# MaTouch_ESP32-S3_AMOLED_AI_CAMERA_v1_1.net
KiCad netlist of a schematic drawn in EAGLE
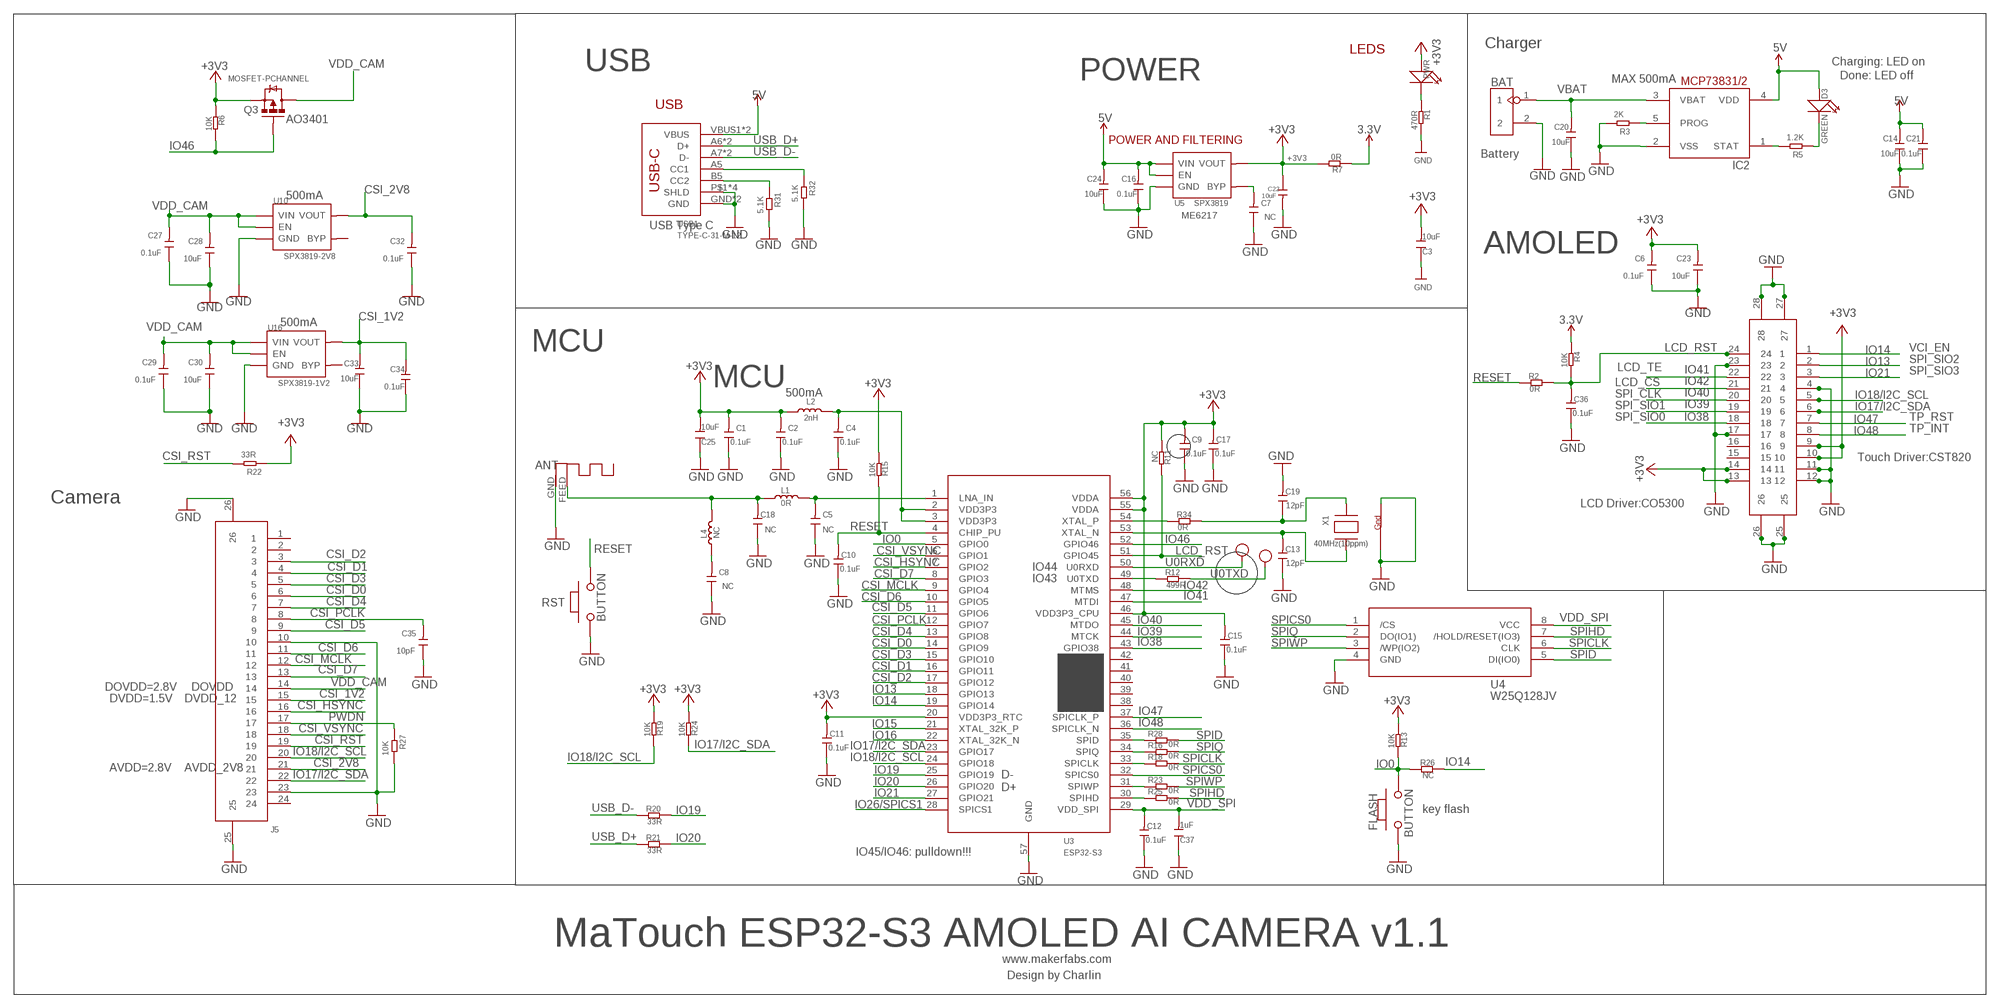
[diagram p0: schematic, sheet 1]

(export (version "E")
  (design (tool "Eeschema 10.0.6"))
  (components
    (comp (ref "ANT1")
      (value "ANTENNA")
      (footprint "eagle-import:RN-ANT")
      (libsource (lib "eagle-import") (part "ANTENNA"))
    )
    (comp (ref "BAT")
      (value "HEADER-2P-2.0")
      (footprint "eagle-import:2P-2.0")
      (libsource (lib "eagle-import") (part "HEADER-2P-2.0"))
    )
    (comp (ref "C1")
      (value "0.1uF")
      (footprint "eagle-import:DISCRETE_C0402")
      (libsource (lib "eagle-import") (part "DISCRETE_C-0402"))
    )
    (comp (ref "C2")
      (value "0.1uF")
      (footprint "eagle-import:DISCRETE_C0402")
      (libsource (lib "eagle-import") (part "DISCRETE_C-0402"))
    )
    (comp (ref "C3")
      (value "10uF")
      (footprint "eagle-import:DISCRETE_C0603")
      (libsource (lib "eagle-import") (part "DISCRETE_C-0603"))
    )
    (comp (ref "C4")
      (value "0.1uF")
      (footprint "eagle-import:DISCRETE_C0402")
      (libsource (lib "eagle-import") (part "DISCRETE_C-0402"))
    )
    (comp (ref "C5")
      (value "NC")
      (footprint "eagle-import:DISCRETE_C0402")
      (libsource (lib "eagle-import") (part "DISCRETE_C-0402"))
    )
    (comp (ref "C6")
      (value "0.1uF")
      (footprint "eagle-import:DISCRETE_C0402")
      (libsource (lib "eagle-import") (part "DISCRETE_C-0402"))
    )
    (comp (ref "C7")
      (value "NC")
      (footprint "eagle-import:DISCRETE_C0402")
      (libsource (lib "eagle-import") (part "DISCRETE_C-0402"))
    )
    (comp (ref "C8")
      (value "NC")
      (footprint "eagle-import:DISCRETE_C0402")
      (libsource (lib "eagle-import") (part "DISCRETE_C-0402"))
    )
    (comp (ref "C9")
      (value "0.1uF")
      (footprint "eagle-import:DISCRETE_C0402")
      (libsource (lib "eagle-import") (part "DISCRETE_C-0402"))
    )
    (comp (ref "C10")
      (value "0.1uF")
      (footprint "eagle-import:DISCRETE_C0402")
      (libsource (lib "eagle-import") (part "DISCRETE_C-0402"))
    )
    (comp (ref "C11")
      (value "0.1uF")
      (footprint "eagle-import:DISCRETE_C0402")
      (libsource (lib "eagle-import") (part "DISCRETE_C-0402"))
    )
    (comp (ref "C12")
      (value "0.1uF")
      (footprint "eagle-import:DISCRETE_C0402")
      (libsource (lib "eagle-import") (part "DISCRETE_C-0402"))
    )
    (comp (ref "C13")
      (value "12pF")
      (footprint "eagle-import:DISCRETE_C0402")
      (libsource (lib "eagle-import") (part "DISCRETE_C-0402"))
    )
    (comp (ref "C14")
      (value "10uF")
      (footprint "eagle-import:DISCRETE_C0402")
      (libsource (lib "eagle-import") (part "DISCRETE_C-0402"))
    )
    (comp (ref "C15")
      (value "0.1uF")
      (footprint "eagle-import:DISCRETE_C0402")
      (libsource (lib "eagle-import") (part "DISCRETE_C-0402"))
    )
    (comp (ref "C16")
      (value "0.1uF")
      (footprint "eagle-import:DISCRETE_C0402")
      (libsource (lib "eagle-import") (part "DISCRETE_C-0402"))
    )
    (comp (ref "C17")
      (value "0.1uF")
      (footprint "eagle-import:DISCRETE_C0402")
      (libsource (lib "eagle-import") (part "DISCRETE_C-0402"))
    )
    (comp (ref "C18")
      (value "NC")
      (footprint "eagle-import:DISCRETE_C0402")
      (libsource (lib "eagle-import") (part "DISCRETE_C-0402"))
    )
    (comp (ref "C19")
      (value "12pF")
      (footprint "eagle-import:DISCRETE_C0402")
      (libsource (lib "eagle-import") (part "DISCRETE_C-0402"))
    )
    (comp (ref "C20")
      (value "10uF")
      (footprint "eagle-import:DISCRETE_C0402")
      (libsource (lib "eagle-import") (part "DISCRETE_C-0402"))
    )
    (comp (ref "C21")
      (value "0.1uF")
      (footprint "eagle-import:DISCRETE_C0402")
      (libsource (lib "eagle-import") (part "DISCRETE_C-0402"))
    )
    (comp (ref "C22")
      (value "10uF")
      (footprint "eagle-import:0603")
      (libsource (lib "eagle-import") (part "C-0603"))
    )
    (comp (ref "C23")
      (value "10uF")
      (footprint "eagle-import:DISCRETE_C0402")
      (libsource (lib "eagle-import") (part "DISCRETE_C-0402"))
    )
    (comp (ref "C24")
      (value "10uF")
      (footprint "eagle-import:DISCRETE_C0402")
      (libsource (lib "eagle-import") (part "DISCRETE_C-0402"))
    )
    (comp (ref "C25")
      (value "10uF")
      (footprint "eagle-import:DISCRETE_C0603")
      (libsource (lib "eagle-import") (part "DISCRETE_C-0603"))
    )
    (comp (ref "C27")
      (value "0.1uF")
      (footprint "eagle-import:DISCRETE_C0402")
      (libsource (lib "eagle-import") (part "DISCRETE_C-0402"))
    )
    (comp (ref "C28")
      (value "10uF")
      (footprint "eagle-import:DISCRETE_C0402")
      (libsource (lib "eagle-import") (part "DISCRETE_C-0402"))
    )
    (comp (ref "C29")
      (value "0.1uF")
      (footprint "eagle-import:DISCRETE_C0402")
      (libsource (lib "eagle-import") (part "DISCRETE_C-0402"))
    )
    (comp (ref "C30")
      (value "10uF")
      (footprint "eagle-import:DISCRETE_C0402")
      (libsource (lib "eagle-import") (part "DISCRETE_C-0402"))
    )
    (comp (ref "C32")
      (value "0.1uF")
      (footprint "eagle-import:DISCRETE_C0402")
      (libsource (lib "eagle-import") (part "DISCRETE_C-0402"))
    )
    (comp (ref "C33")
      (value "10uF")
      (footprint "eagle-import:DISCRETE_C0402")
      (libsource (lib "eagle-import") (part "DISCRETE_C-0402"))
    )
    (comp (ref "C34")
      (value "0.1uF")
      (footprint "eagle-import:DISCRETE_C0402")
      (libsource (lib "eagle-import") (part "DISCRETE_C-0402"))
    )
    (comp (ref "C35")
      (value "10pF")
      (footprint "eagle-import:DISCRETE_C0402")
      (libsource (lib "eagle-import") (part "DISCRETE_C-0402"))
    )
    (comp (ref "C36")
      (value "0.1uF")
      (footprint "eagle-import:DISCRETE_C0402")
      (libsource (lib "eagle-import") (part "DISCRETE_C-0402"))
    )
    (comp (ref "C37")
      (value "1uF")
      (footprint "eagle-import:DISCRETE_C0603")
      (libsource (lib "eagle-import") (part "DISCRETE_C-0603"))
    )
    (comp (ref "D3")
      (value "GREEN")
      (footprint "eagle-import:DISCRETE_LED-0603")
      (libsource (lib "eagle-import") (part "DISCRETE_LED0603"))
    )
    (comp (ref "FLASH")
      (value "BUTTON")
      (footprint "eagle-import:157SW")
      (libsource (lib "eagle-import") (part "PB157"))
    )
    (comp (ref "IC2")
      (value "TP4054")
      (footprint "eagle-import:SOT23-5L")
      (libsource (lib "eagle-import") (part "MCP73831/OT"))
    )
    (comp (ref "J1")
      (value "OK-14GF024-04/AXE524127")
      (footprint "eagle-import:SMD24-50P-730L250W77H")
      (libsource (lib "eagle-import") (part "AXE524127"))
    )
    (comp (ref "J5")
      (value "FPC-24P")
      (footprint "eagle-import:SMD26-50P-1760L450W")
      (libsource (lib "eagle-import") (part "FPC-24P"))
    )
    (comp (ref "L1")
      (value "0R")
      (footprint "eagle-import:DISCRETE_L0402")
      (libsource (lib "eagle-import") (part "DISCRETE_L0402"))
    )
    (comp (ref "L2")
      (value "2nH")
      (footprint "eagle-import:DISCRETE_L0603")
      (libsource (lib "eagle-import") (part "DISCRETE_L0603"))
    )
    (comp (ref "L4")
      (value "NC")
      (footprint "eagle-import:DISCRETE_L0402")
      (libsource (lib "eagle-import") (part "DISCRETE_L0402"))
    )
    (comp (ref "PWR")
      (value "DISCRETE_LED0603")
      (footprint "eagle-import:DISCRETE_LED-0603")
      (libsource (lib "eagle-import") (part "DISCRETE_LED0603"))
    )
    (comp (ref "Q3")
      (value "MOSFET-PCHANNEL")
      (footprint "eagle-import:SOT23-3")
      (libsource (lib "eagle-import") (part "MOSFET-PCHANNEL"))
    )
    (comp (ref "R1")
      (value "470R")
      (footprint "eagle-import:DISCRETE_R0402")
      (libsource (lib "eagle-import") (part "DISCRETE_R-0402"))
    )
    (comp (ref "R2")
      (value "0R")
      (footprint "eagle-import:DISCRETE_R0402")
      (libsource (lib "eagle-import") (part "DISCRETE_R-0402"))
    )
    (comp (ref "R3")
      (value "2K")
      (footprint "eagle-import:DISCRETE_R0402")
      (libsource (lib "eagle-import") (part "DISCRETE_R-0402"))
    )
    (comp (ref "R4")
      (value "10K")
      (footprint "eagle-import:DISCRETE_R0402")
      (libsource (lib "eagle-import") (part "DISCRETE_R-0402"))
    )
    (comp (ref "R5")
      (value "1.2K")
      (footprint "eagle-import:DISCRETE_R0402")
      (libsource (lib "eagle-import") (part "DISCRETE_R-0402"))
    )
    (comp (ref "R6")
      (value "10K")
      (footprint "eagle-import:DISCRETE_R0402")
      (libsource (lib "eagle-import") (part "DISCRETE_R-0402"))
    )
    (comp (ref "R7")
      (value "0R")
      (footprint "eagle-import:DISCRETE_R0402")
      (libsource (lib "eagle-import") (part "DISCRETE_R-0402"))
    )
    (comp (ref "R11")
      (value "NC")
      (footprint "eagle-import:DISCRETE_R0402")
      (libsource (lib "eagle-import") (part "DISCRETE_R-0402"))
    )
    (comp (ref "R12")
      (value "499R")
      (footprint "eagle-import:DISCRETE_R0402")
      (libsource (lib "eagle-import") (part "DISCRETE_R-0402"))
    )
    (comp (ref "R13")
      (value "10K")
      (footprint "eagle-import:DISCRETE_R0402")
      (libsource (lib "eagle-import") (part "DISCRETE_R-0402"))
    )
    (comp (ref "R15")
      (value "10K")
      (footprint "eagle-import:DISCRETE_R0402")
      (libsource (lib "eagle-import") (part "DISCRETE_R-0402"))
    )
    (comp (ref "R16")
      (value "0R")
      (footprint "eagle-import:DISCRETE_R0402")
      (libsource (lib "eagle-import") (part "DISCRETE_R-0402"))
    )
    (comp (ref "R18")
      (value "0R")
      (footprint "eagle-import:DISCRETE_R0402")
      (libsource (lib "eagle-import") (part "DISCRETE_R-0402"))
    )
    (comp (ref "R19")
      (value "10K")
      (footprint "eagle-import:DISCRETE_R0402")
      (libsource (lib "eagle-import") (part "DISCRETE_R-0402"))
    )
    (comp (ref "R20")
      (value "33R")
      (footprint "eagle-import:DISCRETE_R0402")
      (libsource (lib "eagle-import") (part "DISCRETE_R-0402"))
    )
    (comp (ref "R21")
      (value "33R")
      (footprint "eagle-import:DISCRETE_R0402")
      (libsource (lib "eagle-import") (part "DISCRETE_R-0402"))
    )
    (comp (ref "R22")
      (value "33R")
      (footprint "eagle-import:DISCRETE_R0402")
      (libsource (lib "eagle-import") (part "DISCRETE_R-0402"))
    )
    (comp (ref "R23")
      (value "0R")
      (footprint "eagle-import:DISCRETE_R0402")
      (libsource (lib "eagle-import") (part "DISCRETE_R-0402"))
    )
    (comp (ref "R24")
      (value "10K")
      (footprint "eagle-import:DISCRETE_R0402")
      (libsource (lib "eagle-import") (part "DISCRETE_R-0402"))
    )
    (comp (ref "R25")
      (value "0R")
      (footprint "eagle-import:DISCRETE_R0402")
      (libsource (lib "eagle-import") (part "DISCRETE_R-0402"))
    )
    (comp (ref "R26")
      (value "NC")
      (footprint "eagle-import:DISCRETE_R0402")
      (libsource (lib "eagle-import") (part "DISCRETE_R-0402"))
    )
    (comp (ref "R27")
      (value "10K")
      (footprint "eagle-import:DISCRETE_R0402")
      (libsource (lib "eagle-import") (part "DISCRETE_R-0402"))
    )
    (comp (ref "R28")
      (value "0R")
      (footprint "eagle-import:DISCRETE_R0402")
      (libsource (lib "eagle-import") (part "DISCRETE_R-0402"))
    )
    (comp (ref "R31")
      (value "5.1K")
      (footprint "eagle-import:DISCRETE_R0402")
      (libsource (lib "eagle-import") (part "DISCRETE_R-0402"))
    )
    (comp (ref "R32")
      (value "5.1K")
      (footprint "eagle-import:DISCRETE_R0402")
      (libsource (lib "eagle-import") (part "DISCRETE_R-0402"))
    )
    (comp (ref "R34")
      (value "0R")
      (footprint "eagle-import:DISCRETE_R0402")
      (libsource (lib "eagle-import") (part "DISCRETE_R-0402"))
    )
    (comp (ref "RST")
      (value "BUTTON")
      (footprint "eagle-import:157SW")
      (libsource (lib "eagle-import") (part "PB157"))
    )
    (comp (ref "RX")
      (value "TEST-POINT'4545'")
      (footprint "eagle-import:TP-D45MIL")
      (fields (field (name "PARTNO") "DNP") (field (name "PARTNO_1") "DNP"))
      (libsource (lib "eagle-import") (part "TEST-POINT'4545'"))
    )
    (comp (ref "TX")
      (value "TEST-POINT'4545'")
      (footprint "eagle-import:TP-D45MIL")
      (fields (field (name "PARTNO") "DNP") (field (name "PARTNO_1") "DNP"))
      (libsource (lib "eagle-import") (part "TEST-POINT'4545'"))
    )
    (comp (ref "U3")
      (value "ESP32-S3")
      (footprint "eagle-import:QFN56-7_7MM")
      (libsource (lib "eagle-import") (part "ESP32-S3"))
    )
    (comp (ref "U4")
      (value "W25Q128JV")
      (footprint "eagle-import:SOIC-8-208MIL")
      (libsource (lib "eagle-import") (part "W25Q128JV"))
    )
    (comp (ref "U5")
      (value "SPX3819")
      (footprint "eagle-import:SOT23-5")
      (libsource (lib "eagle-import") (part "SPX3819"))
    )
    (comp (ref "U10")
      (value "SPX3819-2V8")
      (footprint "eagle-import:SOT23-5")
      (libsource (lib "eagle-import") (part "SPX3819"))
    )
    (comp (ref "U16")
      (value "SPX3819-1V2")
      (footprint "eagle-import:SOT23-5")
      (libsource (lib "eagle-import") (part "SPX3819"))
    )
    (comp (ref "USB1")
      (value "TYPE-C-31-M-12")
      (footprint "eagle-import:TYPE-C-31-M-12")
      (libsource (lib "eagle-import") (part "TYPE-C-31-M-12"))
    )
    (comp (ref "X1")
      (value "40MHz(10ppm)")
      (footprint "eagle-import:NX3225")
      (libsource (lib "eagle-import") (part "XTAL-4-3225"))
    )
  )
  (nets
    (net (code "1") (name "+3V3") (class "Default")
      (node (ref "C1") (pin "2") (pinfunction "2_2") (pintype "passive"))
      (node (ref "C11") (pin "2") (pinfunction "2_2") (pintype "passive"))
      (node (ref "C15") (pin "2") (pinfunction "2_2") (pintype "passive"))
      (node (ref "C17") (pin "2") (pinfunction "2_2") (pintype "passive"))
      (node (ref "C2") (pin "2") (pinfunction "2_2") (pintype "passive"))
      (node (ref "C22") (pin "1") (pinfunction "1_1") (pintype "passive"))
      (node (ref "C23") (pin "2") (pinfunction "2_2") (pintype "passive"))
      (node (ref "C25") (pin "2") (pinfunction "2_2") (pintype "passive"))
      (node (ref "C3") (pin "2") (pinfunction "2_2") (pintype "passive"))
      (node (ref "C6") (pin "2") (pinfunction "2_2") (pintype "passive"))
      (node (ref "C9") (pin "2") (pinfunction "2_2") (pintype "passive"))
      (node (ref "J1") (pin "10") (pinfunction "10_10") (pintype "bidirectional"))
      (node (ref "J1") (pin "13") (pinfunction "13_13") (pintype "bidirectional"))
      (node (ref "J1") (pin "14") (pinfunction "14_14") (pintype "bidirectional"))
      (node (ref "J1") (pin "9") (pinfunction "9_9") (pintype "bidirectional"))
      (node (ref "L2") (pin "1") (pinfunction "1_1") (pintype "passive"))
      (node (ref "PWR") (pin "+") (pinfunction "+_+") (pintype "passive"))
      (node (ref "Q3") (pin "2") (pinfunction "S_2") (pintype "passive"))
      (node (ref "R11") (pin "2") (pinfunction "2_2") (pintype "passive"))
      (node (ref "R13") (pin "2") (pinfunction "2_2") (pintype "passive"))
      (node (ref "R15") (pin "2") (pinfunction "2_2") (pintype "passive"))
      (node (ref "R19") (pin "2") (pinfunction "2_2") (pintype "passive"))
      (node (ref "R22") (pin "1") (pinfunction "1_1") (pintype "passive"))
      (node (ref "R24") (pin "2") (pinfunction "2_2") (pintype "passive"))
      (node (ref "R6") (pin "2") (pinfunction "2_2") (pintype "passive"))
      (node (ref "R7") (pin "1") (pinfunction "1_1") (pintype "passive"))
      (node (ref "U3") (pin "20") (pinfunction "VDD3P3_RTC_20") (pintype "bidirectional"))
      (node (ref "U3") (pin "46") (pinfunction "VDD3P3_CPU_46") (pintype "bidirectional"))
      (node (ref "U3") (pin "55") (pinfunction "VDDA_55") (pintype "bidirectional"))
      (node (ref "U3") (pin "56") (pinfunction "VDDA_56") (pintype "bidirectional"))
      (node (ref "U5") (pin "5") (pinfunction "VOUT_5") (pintype "bidirectional"))
    )
    (net (code "2") (name "/CSI_1V2") (class "Default")
      (node (ref "C33") (pin "2") (pinfunction "2_2") (pintype "passive"))
      (node (ref "C34") (pin "2") (pinfunction "2_2") (pintype "passive"))
      (node (ref "J5") (pin "15") (pinfunction "15_15") (pintype "bidirectional"))
      (node (ref "U16") (pin "5") (pinfunction "VOUT_5") (pintype "bidirectional"))
    )
    (net (code "3") (name "/CSI_2V8") (class "Default")
      (node (ref "C32") (pin "2") (pinfunction "2_2") (pintype "passive"))
      (node (ref "J5") (pin "21") (pinfunction "21_21") (pintype "bidirectional"))
      (node (ref "U10") (pin "5") (pinfunction "VOUT_5") (pintype "bidirectional"))
    )
    (net (code "4") (name "/CSI_D0") (class "Default")
      (node (ref "J5") (pin "6") (pinfunction "6_6") (pintype "bidirectional"))
      (node (ref "U3") (pin "14") (pinfunction "GPIO9_14") (pintype "bidirectional"))
    )
    (net (code "5") (name "/CSI_D1") (class "Default")
      (node (ref "J5") (pin "4") (pinfunction "4_4") (pintype "bidirectional"))
      (node (ref "U3") (pin "16") (pinfunction "GPIO11_16") (pintype "bidirectional"))
    )
    (net (code "6") (name "/CSI_D2") (class "Default")
      (node (ref "J5") (pin "3") (pinfunction "3_3") (pintype "bidirectional"))
      (node (ref "U3") (pin "17") (pinfunction "GPIO12_17") (pintype "bidirectional"))
    )
    (net (code "7") (name "/CSI_D3") (class "Default")
      (node (ref "J5") (pin "5") (pinfunction "5_5") (pintype "bidirectional"))
      (node (ref "U3") (pin "15") (pinfunction "GPIO10_15") (pintype "bidirectional"))
    )
    (net (code "8") (name "/CSI_D4") (class "Default")
      (node (ref "J5") (pin "7") (pinfunction "7_7") (pintype "bidirectional"))
      (node (ref "U3") (pin "13") (pinfunction "GPIO8_13") (pintype "bidirectional"))
    )
    (net (code "9") (name "/CSI_D5") (class "Default")
      (node (ref "J5") (pin "9") (pinfunction "9_9") (pintype "bidirectional"))
      (node (ref "U3") (pin "11") (pinfunction "GPIO6_11") (pintype "bidirectional"))
    )
    (net (code "10") (name "/CSI_D6") (class "Default")
      (node (ref "J5") (pin "11") (pinfunction "11_11") (pintype "bidirectional"))
      (node (ref "U3") (pin "10") (pinfunction "GPIO5_10") (pintype "bidirectional"))
    )
    (net (code "11") (name "/CSI_D7") (class "Default")
      (node (ref "J5") (pin "13") (pinfunction "13_13") (pintype "bidirectional"))
      (node (ref "U3") (pin "8") (pinfunction "GPIO3_8") (pintype "bidirectional"))
    )
    (net (code "12") (name "/CSI_HSYNC") (class "Default")
      (node (ref "J5") (pin "16") (pinfunction "16_16") (pintype "bidirectional"))
      (node (ref "U3") (pin "7") (pinfunction "GPIO2_7") (pintype "bidirectional"))
    )
    (net (code "13") (name "/CSI_MCLK") (class "Default")
      (node (ref "J5") (pin "12") (pinfunction "12_12") (pintype "bidirectional"))
      (node (ref "U3") (pin "9") (pinfunction "GPIO4_9") (pintype "bidirectional"))
    )
    (net (code "14") (name "/CSI_PCLK") (class "Default")
      (node (ref "C35") (pin "2") (pinfunction "2_2") (pintype "passive"))
      (node (ref "J5") (pin "8") (pinfunction "8_8") (pintype "bidirectional"))
      (node (ref "U3") (pin "12") (pinfunction "GPIO7_12") (pintype "bidirectional"))
    )
    (net (code "15") (name "/CSI_RST") (class "Default")
      (node (ref "J5") (pin "19") (pinfunction "19_19") (pintype "bidirectional"))
      (node (ref "R22") (pin "2") (pinfunction "2_2") (pintype "passive"))
    )
    (net (code "16") (name "/CSI_VSYNC") (class "Default")
      (node (ref "J5") (pin "18") (pinfunction "18_18") (pintype "bidirectional"))
      (node (ref "U3") (pin "6") (pinfunction "GPIO1_6") (pintype "bidirectional"))
    )
    (net (code "17") (name "/IO0") (class "Default")
      (node (ref "FLASH") (pin "2") (pinfunction "2_2") (pintype "passive"))
      (node (ref "R13") (pin "1") (pinfunction "1_1") (pintype "passive"))
      (node (ref "R26") (pin "2") (pinfunction "2_2") (pintype "passive"))
      (node (ref "U3") (pin "5") (pinfunction "GPIO0_5") (pintype "bidirectional"))
    )
    (net (code "18") (name "/IO13") (class "Default")
      (node (ref "J1") (pin "2") (pinfunction "2_2") (pintype "bidirectional"))
      (node (ref "U3") (pin "18") (pinfunction "GPIO13_18") (pintype "bidirectional"))
    )
    (net (code "19") (name "/IO14") (class "Default")
      (node (ref "J1") (pin "1") (pinfunction "1_1") (pintype "bidirectional"))
      (node (ref "R26") (pin "1") (pinfunction "1_1") (pintype "passive"))
      (node (ref "U3") (pin "19") (pinfunction "GPIO14_19") (pintype "bidirectional"))
    )
    (net (code "20") (name "/IO15") (class "Default")
      (node (ref "U3") (pin "21") (pinfunction "XTAL_32K_P_21") (pintype "bidirectional"))
    )
    (net (code "21") (name "/IO16") (class "Default")
      (node (ref "U3") (pin "22") (pinfunction "XTAL_32K_N_22") (pintype "bidirectional"))
    )
    (net (code "22") (name "/IO17{slash}I2C_SDA") (class "Default")
      (node (ref "J1") (pin "6") (pinfunction "6_6") (pintype "bidirectional"))
      (node (ref "J5") (pin "22") (pinfunction "22_22") (pintype "bidirectional"))
      (node (ref "R24") (pin "1") (pinfunction "1_1") (pintype "passive"))
      (node (ref "U3") (pin "23") (pinfunction "GPIO17_23") (pintype "bidirectional"))
    )
    (net (code "23") (name "/IO18{slash}I2C_SCL") (class "Default")
      (node (ref "J1") (pin "5") (pinfunction "5_5") (pintype "bidirectional"))
      (node (ref "J5") (pin "20") (pinfunction "20_20") (pintype "bidirectional"))
      (node (ref "R19") (pin "1") (pinfunction "1_1") (pintype "passive"))
      (node (ref "U3") (pin "24") (pinfunction "GPIO18_24") (pintype "bidirectional"))
    )
    (net (code "24") (name "/IO19") (class "Default")
      (node (ref "R20") (pin "1") (pinfunction "1_1") (pintype "passive"))
      (node (ref "U3") (pin "25") (pinfunction "GPIO19_25") (pintype "bidirectional"))
    )
    (net (code "25") (name "/IO20") (class "Default")
      (node (ref "R21") (pin "1") (pinfunction "1_1") (pintype "passive"))
      (node (ref "U3") (pin "26") (pinfunction "GPIO20_26") (pintype "bidirectional"))
    )
    (net (code "26") (name "/IO21") (class "Default")
      (node (ref "J1") (pin "3") (pinfunction "3_3") (pintype "bidirectional"))
      (node (ref "U3") (pin "27") (pinfunction "GPIO21_27") (pintype "bidirectional"))
    )
    (net (code "27") (name "/IO26{slash}SPICS1") (class "Default")
      (node (ref "U3") (pin "28") (pinfunction "SPICS1_28") (pintype "bidirectional"))
    )
    (net (code "28") (name "/IO38") (class "Default")
      (node (ref "J1") (pin "18") (pinfunction "18_18") (pintype "bidirectional"))
      (node (ref "U3") (pin "43") (pinfunction "GPIO38_43") (pintype "bidirectional"))
    )
    (net (code "29") (name "/IO39") (class "Default")
      (node (ref "J1") (pin "19") (pinfunction "19_19") (pintype "bidirectional"))
      (node (ref "U3") (pin "44") (pinfunction "MTCK_44") (pintype "bidirectional"))
    )
    (net (code "30") (name "/IO40") (class "Default")
      (node (ref "J1") (pin "20") (pinfunction "20_20") (pintype "bidirectional"))
      (node (ref "U3") (pin "45") (pinfunction "MTDO_45") (pintype "bidirectional"))
    )
    (net (code "31") (name "/IO41") (class "Default")
      (node (ref "J1") (pin "22") (pinfunction "22_22") (pintype "bidirectional"))
      (node (ref "U3") (pin "47") (pinfunction "MTDI_47") (pintype "bidirectional"))
    )
    (net (code "32") (name "/IO42") (class "Default")
      (node (ref "J1") (pin "21") (pinfunction "21_21") (pintype "bidirectional"))
      (node (ref "U3") (pin "48") (pinfunction "MTMS_48") (pintype "bidirectional"))
    )
    (net (code "33") (name "/IO46") (class "Default")
      (node (ref "Q3") (pin "1") (pinfunction "G_1") (pintype "passive"))
      (node (ref "R6") (pin "1") (pinfunction "1_1") (pintype "passive"))
      (node (ref "U3") (pin "52") (pinfunction "GPIO46_52") (pintype "bidirectional"))
    )
    (net (code "34") (name "/IO47") (class "Default")
      (node (ref "J1") (pin "7") (pinfunction "7_7") (pintype "bidirectional"))
      (node (ref "U3") (pin "37") (pinfunction "SPICLK_P_37") (pintype "bidirectional"))
    )
    (net (code "35") (name "/IO48") (class "Default")
      (node (ref "J1") (pin "8") (pinfunction "8_8") (pintype "bidirectional"))
      (node (ref "U3") (pin "36") (pinfunction "SPICLK_N_36") (pintype "bidirectional"))
    )
    (net (code "36") (name "/LCD_RST") (class "Default")
      (node (ref "C36") (pin "2") (pinfunction "2_2") (pintype "passive"))
      (node (ref "J1") (pin "24") (pinfunction "24_24") (pintype "bidirectional"))
      (node (ref "R11") (pin "1") (pinfunction "1_1") (pintype "passive"))
      (node (ref "R2") (pin "1") (pinfunction "1_1") (pintype "passive"))
      (node (ref "R4") (pin "1") (pinfunction "1_1") (pintype "passive"))
      (node (ref "U3") (pin "51") (pinfunction "GPIO45_51") (pintype "bidirectional"))
    )
    (net (code "37") (name "/PWDN") (class "Default")
      (node (ref "J5") (pin "17") (pinfunction "17_17") (pintype "bidirectional"))
      (node (ref "R27") (pin "1") (pinfunction "1_1") (pintype "passive"))
    )
    (net (code "38") (name "/RESET") (class "Default")
      (node (ref "C10") (pin "2") (pinfunction "2_2") (pintype "passive"))
      (node (ref "R15") (pin "1") (pinfunction "1_1") (pintype "passive"))
      (node (ref "R2") (pin "2") (pinfunction "2_2") (pintype "passive"))
      (node (ref "RST") (pin "2") (pinfunction "2_2") (pintype "passive"))
      (node (ref "U3") (pin "4") (pinfunction "CHIP_PU_4") (pintype "bidirectional"))
    )
    (net (code "39") (name "/SPICLK") (class "Default")
      (node (ref "R18") (pin "1") (pinfunction "1_1") (pintype "passive"))
      (node (ref "U4") (pin "6") (pinfunction "CLK_6") (pintype "bidirectional"))
    )
    (net (code "40") (name "/SPICS0") (class "Default")
      (node (ref "U3") (pin "32") (pinfunction "SPICS0_32") (pintype "bidirectional"))
      (node (ref "U4") (pin "1") (pinfunction "/CS_1") (pintype "bidirectional"))
    )
    (net (code "41") (name "/SPID") (class "Default")
      (node (ref "R28") (pin "1") (pinfunction "1_1") (pintype "passive"))
      (node (ref "U4") (pin "5") (pinfunction "DI(IO0)_5") (pintype "bidirectional"))
    )
    (net (code "42") (name "/SPIHD") (class "Default")
      (node (ref "R25") (pin "1") (pinfunction "1_1") (pintype "passive"))
      (node (ref "U4") (pin "7") (pinfunction "/HOLD/RESET(IO3)_7") (pintype "bidirectional"))
    )
    (net (code "43") (name "/SPIQ") (class "Default")
      (node (ref "R16") (pin "1") (pinfunction "1_1") (pintype "passive"))
      (node (ref "U4") (pin "2") (pinfunction "DO(IO1)_2") (pintype "bidirectional"))
    )
    (net (code "44") (name "/SPIWP") (class "Default")
      (node (ref "R23") (pin "1") (pinfunction "1_1") (pintype "passive"))
      (node (ref "U4") (pin "3") (pinfunction "/WP(IO2)_3") (pintype "bidirectional"))
    )
    (net (code "45") (name "/U0RXD") (class "Default")
      (node (ref "RX") (pin "T") (pinfunction "T_T") (pintype "bidirectional"))
      (node (ref "U3") (pin "50") (pinfunction "U0RXD_50") (pintype "bidirectional"))
    )
    (net (code "46") (name "/U0TXD") (class "Default")
      (node (ref "R12") (pin "1") (pinfunction "1_1") (pintype "passive"))
      (node (ref "TX") (pin "T") (pinfunction "T_T") (pintype "bidirectional"))
    )
    (net (code "47") (name "/USB_D+") (class "Default")
      (node (ref "R21") (pin "2") (pinfunction "2_2") (pintype "passive"))
      (node (ref "USB1") (pin "A6") (pinfunction "D+_A6") (pintype "bidirectional"))
      (node (ref "USB1") (pin "B6") (pinfunction "D+_B6") (pintype "bidirectional"))
    )
    (net (code "48") (name "/USB_D-") (class "Default")
      (node (ref "R20") (pin "2") (pinfunction "2_2") (pintype "passive"))
      (node (ref "USB1") (pin "A7") (pinfunction "D-_A7") (pintype "bidirectional"))
      (node (ref "USB1") (pin "B7") (pinfunction "D-_B7") (pintype "bidirectional"))
    )
    (net (code "49") (name "/VBAT") (class "Default")
      (node (ref "BAT") (pin "1") (pinfunction "1_1") (pintype "bidirectional"))
      (node (ref "C20") (pin "2") (pinfunction "2_2") (pintype "passive"))
      (node (ref "IC2") (pin "3") (pinfunction "VBAT_3") (pintype "bidirectional"))
    )
    (net (code "50") (name "/VDD_CAM") (class "Default")
      (node (ref "C27") (pin "2") (pinfunction "2_2") (pintype "passive"))
      (node (ref "C28") (pin "2") (pinfunction "2_2") (pintype "passive"))
      (node (ref "C29") (pin "2") (pinfunction "2_2") (pintype "passive"))
      (node (ref "C30") (pin "2") (pinfunction "2_2") (pintype "passive"))
      (node (ref "J5") (pin "14") (pinfunction "14_14") (pintype "bidirectional"))
      (node (ref "Q3") (pin "3") (pinfunction "D_3") (pintype "passive"))
      (node (ref "U10") (pin "1") (pinfunction "VIN_1") (pintype "bidirectional"))
      (node (ref "U10") (pin "3") (pinfunction "EN_3") (pintype "bidirectional"))
      (node (ref "U16") (pin "1") (pinfunction "VIN_1") (pintype "bidirectional"))
      (node (ref "U16") (pin "3") (pinfunction "EN_3") (pintype "bidirectional"))
    )
    (net (code "51") (name "/VDD_SPI") (class "Default")
      (node (ref "C12") (pin "2") (pinfunction "2_2") (pintype "passive"))
      (node (ref "C37") (pin "2") (pinfunction "2_2") (pintype "passive"))
      (node (ref "U3") (pin "29") (pinfunction "VDD_SPI_29") (pintype "bidirectional"))
      (node (ref "U4") (pin "8") (pinfunction "VCC_8") (pintype "bidirectional"))
    )
    (net (code "52") (name "3.3V") (class "Default")
      (node (ref "R4") (pin "2") (pinfunction "2_2") (pintype "passive"))
      (node (ref "R7") (pin "2") (pinfunction "2_2") (pintype "passive"))
    )
    (net (code "53") (name "5V") (class "Default")
      (node (ref "C14") (pin "2") (pinfunction "2_2") (pintype "passive"))
      (node (ref "C16") (pin "2") (pinfunction "2_2") (pintype "passive"))
      (node (ref "C21") (pin "2") (pinfunction "2_2") (pintype "passive"))
      (node (ref "C24") (pin "2") (pinfunction "2_2") (pintype "passive"))
      (node (ref "D3") (pin "+") (pinfunction "+_+") (pintype "passive"))
      (node (ref "IC2") (pin "4") (pinfunction "VDD_4") (pintype "power_in"))
      (node (ref "U5") (pin "1") (pinfunction "VIN_1") (pintype "bidirectional"))
      (node (ref "U5") (pin "3") (pinfunction "EN_3") (pintype "bidirectional"))
      (node (ref "USB1") (pin "VBUS1") (pinfunction "VBUS_VBUS1") (pintype "bidirectional"))
      (node (ref "USB1") (pin "VBUS2") (pinfunction "VBUS_VBUS2") (pintype "bidirectional"))
    )
    (net (code "54") (name "GND") (class "Default")
      (node (ref "ANT1") (pin "GND") (pinfunction "GND_GND") (pintype "passive"))
      (node (ref "BAT") (pin "2") (pinfunction "2_2") (pintype "bidirectional"))
      (node (ref "C1") (pin "1") (pinfunction "1_1") (pintype "passive"))
      (node (ref "C10") (pin "1") (pinfunction "1_1") (pintype "passive"))
      (node (ref "C11") (pin "1") (pinfunction "1_1") (pintype "passive"))
      (node (ref "C12") (pin "1") (pinfunction "1_1") (pintype "passive"))
      (node (ref "C13") (pin "1") (pinfunction "1_1") (pintype "passive"))
      (node (ref "C14") (pin "1") (pinfunction "1_1") (pintype "passive"))
      (node (ref "C15") (pin "1") (pinfunction "1_1") (pintype "passive"))
      (node (ref "C16") (pin "1") (pinfunction "1_1") (pintype "passive"))
      (node (ref "C17") (pin "1") (pinfunction "1_1") (pintype "passive"))
      (node (ref "C18") (pin "1") (pinfunction "1_1") (pintype "passive"))
      (node (ref "C19") (pin "2") (pinfunction "2_2") (pintype "passive"))
      (node (ref "C2") (pin "1") (pinfunction "1_1") (pintype "passive"))
      (node (ref "C20") (pin "1") (pinfunction "1_1") (pintype "passive"))
      (node (ref "C21") (pin "1") (pinfunction "1_1") (pintype "passive"))
      (node (ref "C22") (pin "2") (pinfunction "2_2") (pintype "passive"))
      (node (ref "C23") (pin "1") (pinfunction "1_1") (pintype "passive"))
      (node (ref "C24") (pin "1") (pinfunction "1_1") (pintype "passive"))
      (node (ref "C25") (pin "1") (pinfunction "1_1") (pintype "passive"))
      (node (ref "C27") (pin "1") (pinfunction "1_1") (pintype "passive"))
      (node (ref "C28") (pin "1") (pinfunction "1_1") (pintype "passive"))
      (node (ref "C29") (pin "1") (pinfunction "1_1") (pintype "passive"))
      (node (ref "C3") (pin "1") (pinfunction "1_1") (pintype "passive"))
      (node (ref "C30") (pin "1") (pinfunction "1_1") (pintype "passive"))
      (node (ref "C32") (pin "1") (pinfunction "1_1") (pintype "passive"))
      (node (ref "C33") (pin "1") (pinfunction "1_1") (pintype "passive"))
      (node (ref "C34") (pin "1") (pinfunction "1_1") (pintype "passive"))
      (node (ref "C35") (pin "1") (pinfunction "1_1") (pintype "passive"))
      (node (ref "C36") (pin "1") (pinfunction "1_1") (pintype "passive"))
      (node (ref "C37") (pin "1") (pinfunction "1_1") (pintype "passive"))
      (node (ref "C4") (pin "1") (pinfunction "1_1") (pintype "passive"))
      (node (ref "C5") (pin "1") (pinfunction "1_1") (pintype "passive"))
      (node (ref "C6") (pin "1") (pinfunction "1_1") (pintype "passive"))
      (node (ref "C7") (pin "1") (pinfunction "1_1") (pintype "passive"))
      (node (ref "C8") (pin "1") (pinfunction "1_1") (pintype "passive"))
      (node (ref "C9") (pin "1") (pinfunction "1_1") (pintype "passive"))
      (node (ref "FLASH") (pin "1") (pinfunction "1_1") (pintype "passive"))
      (node (ref "IC2") (pin "2") (pinfunction "VSS_2") (pintype "power_in"))
      (node (ref "J1") (pin "11") (pinfunction "11_11") (pintype "bidirectional"))
      (node (ref "J1") (pin "12") (pinfunction "12_12") (pintype "bidirectional"))
      (node (ref "J1") (pin "17") (pinfunction "17_17") (pintype "bidirectional"))
      (node (ref "J1") (pin "23") (pinfunction "23_23") (pintype "bidirectional"))
      (node (ref "J1") (pin "25") (pinfunction "25_25") (pintype "bidirectional"))
      (node (ref "J1") (pin "26") (pinfunction "26_26") (pintype "bidirectional"))
      (node (ref "J1") (pin "27") (pinfunction "27_27") (pintype "bidirectional"))
      (node (ref "J1") (pin "28") (pinfunction "28_28") (pintype "bidirectional"))
      (node (ref "J1") (pin "4") (pinfunction "4_4") (pintype "bidirectional"))
      (node (ref "J5") (pin "10") (pinfunction "10_10") (pintype "bidirectional"))
      (node (ref "J5") (pin "23") (pinfunction "23_23") (pintype "bidirectional"))
      (node (ref "J5") (pin "25") (pinfunction "25_25") (pintype "bidirectional"))
      (node (ref "J5") (pin "26") (pinfunction "26_26") (pintype "bidirectional"))
      (node (ref "R1") (pin "1") (pinfunction "1_1") (pintype "passive"))
      (node (ref "R27") (pin "2") (pinfunction "2_2") (pintype "passive"))
      (node (ref "R3") (pin "2") (pinfunction "2_2") (pintype "passive"))
      (node (ref "R31") (pin "2") (pinfunction "2_2") (pintype "passive"))
      (node (ref "R32") (pin "2") (pinfunction "2_2") (pintype "passive"))
      (node (ref "RST") (pin "1") (pinfunction "1_1") (pintype "passive"))
      (node (ref "U10") (pin "2") (pinfunction "GND_2") (pintype "bidirectional"))
      (node (ref "U16") (pin "2") (pinfunction "GND_2") (pintype "bidirectional"))
      (node (ref "U3") (pin "57") (pinfunction "GND_57") (pintype "bidirectional"))
      (node (ref "U4") (pin "4") (pinfunction "GND_4") (pintype "bidirectional"))
      (node (ref "U5") (pin "2") (pinfunction "GND_2") (pintype "bidirectional"))
      (node (ref "USB1") (pin "GND") (pinfunction "GND_GND") (pintype "bidirectional"))
      (node (ref "USB1") (pin "GND2") (pinfunction "GND_GND2") (pintype "bidirectional"))
      (node (ref "USB1") (pin "P$1") (pinfunction "SHLD_P$1") (pintype "bidirectional"))
      (node (ref "USB1") (pin "P$2") (pinfunction "SHLD_P$2") (pintype "bidirectional"))
      (node (ref "USB1") (pin "P$3") (pinfunction "SHLD_P$3") (pintype "bidirectional"))
      (node (ref "USB1") (pin "P$4") (pinfunction "SHLD_P$4") (pintype "bidirectional"))
      (node (ref "X1") (pin "2") (pinfunction "G2_2") (pintype "power_in"))
      (node (ref "X1") (pin "4") (pinfunction "G1_4") (pintype "power_in"))
    )
    (net (code "55") (name "Net-(ANT1-PadFEED)") (class "Default")
      (node (ref "ANT1") (pin "FEED") (pinfunction "FEED_FEED") (pintype "passive"))
      (node (ref "C18") (pin "2") (pinfunction "2_2") (pintype "passive"))
      (node (ref "L1") (pin "1") (pinfunction "1_1") (pintype "passive"))
      (node (ref "L4") (pin "2") (pinfunction "2_2") (pintype "passive"))
    )
    (net (code "56") (name "Net-(C4-Pad2)") (class "Default")
      (node (ref "C4") (pin "2") (pinfunction "2_2") (pintype "passive"))
      (node (ref "L2") (pin "2") (pinfunction "2_2") (pintype "passive"))
      (node (ref "U3") (pin "2") (pinfunction "VDD3P3_2") (pintype "bidirectional"))
      (node (ref "U3") (pin "3") (pinfunction "VDD3P3_3") (pintype "bidirectional"))
    )
    (net (code "57") (name "Net-(C8-Pad2)") (class "Default")
      (node (ref "C8") (pin "2") (pinfunction "2_2") (pintype "passive"))
      (node (ref "L4") (pin "1") (pinfunction "1_1") (pintype "passive"))
    )
    (net (code "58") (name "Net-(D3-Pad-)") (class "Default")
      (node (ref "D3") (pin "-") (pinfunction "-_-") (pintype "passive"))
      (node (ref "R5") (pin "1") (pinfunction "1_1") (pintype "passive"))
    )
    (net (code "59") (name "Net-(IC2-PROG)") (class "Default")
      (node (ref "IC2") (pin "5") (pinfunction "PROG_5") (pintype "input"))
      (node (ref "R3") (pin "1") (pinfunction "1_1") (pintype "passive"))
    )
    (net (code "60") (name "Net-(IC2-STAT)") (class "Default")
      (node (ref "IC2") (pin "1") (pinfunction "STAT_1") (pintype "output"))
      (node (ref "R5") (pin "2") (pinfunction "2_2") (pintype "passive"))
    )
    (net (code "61") (name "Net-(PWR-Pad-)") (class "Default")
      (node (ref "PWR") (pin "-") (pinfunction "-_-") (pintype "passive"))
      (node (ref "R1") (pin "2") (pinfunction "2_2") (pintype "passive"))
    )
    (net (code "62") (name "Net-(U3-LNA_IN)") (class "Default")
      (node (ref "C5") (pin "2") (pinfunction "2_2") (pintype "passive"))
      (node (ref "L1") (pin "2") (pinfunction "2_2") (pintype "passive"))
      (node (ref "U3") (pin "1") (pinfunction "LNA_IN_1") (pintype "bidirectional"))
    )
    (net (code "63") (name "Net-(U3-SPICLK)") (class "Default")
      (node (ref "R18") (pin "2") (pinfunction "2_2") (pintype "passive"))
      (node (ref "U3") (pin "33") (pinfunction "SPICLK_33") (pintype "bidirectional"))
    )
    (net (code "64") (name "Net-(U3-SPID)") (class "Default")
      (node (ref "R28") (pin "2") (pinfunction "2_2") (pintype "passive"))
      (node (ref "U3") (pin "35") (pinfunction "SPID_35") (pintype "bidirectional"))
    )
    (net (code "65") (name "Net-(U3-SPIHD)") (class "Default")
      (node (ref "R25") (pin "2") (pinfunction "2_2") (pintype "passive"))
      (node (ref "U3") (pin "30") (pinfunction "SPIHD_30") (pintype "bidirectional"))
    )
    (net (code "66") (name "Net-(U3-SPIQ)") (class "Default")
      (node (ref "R16") (pin "2") (pinfunction "2_2") (pintype "passive"))
      (node (ref "U3") (pin "34") (pinfunction "SPIQ_34") (pintype "bidirectional"))
    )
    (net (code "67") (name "Net-(U3-SPIWP)") (class "Default")
      (node (ref "R23") (pin "2") (pinfunction "2_2") (pintype "passive"))
      (node (ref "U3") (pin "31") (pinfunction "SPIWP_31") (pintype "bidirectional"))
    )
    (net (code "68") (name "Net-(U3-U0TXD)") (class "Default")
      (node (ref "R12") (pin "2") (pinfunction "2_2") (pintype "passive"))
      (node (ref "U3") (pin "49") (pinfunction "U0TXD_49") (pintype "bidirectional"))
    )
    (net (code "69") (name "Net-(U3-XTAL_N)") (class "Default")
      (node (ref "C13") (pin "2") (pinfunction "2_2") (pintype "passive"))
      (node (ref "U3") (pin "53") (pinfunction "XTAL_N_53") (pintype "bidirectional"))
      (node (ref "X1") (pin "3") (pinfunction "X2_3") (pintype "bidirectional"))
    )
    (net (code "70") (name "Net-(U3-XTAL_P)") (class "Default")
      (node (ref "R34") (pin "2") (pinfunction "2_2") (pintype "passive"))
      (node (ref "U3") (pin "54") (pinfunction "XTAL_P_54") (pintype "bidirectional"))
    )
    (net (code "71") (name "Net-(U5-BYP)") (class "Default")
      (node (ref "C7") (pin "2") (pinfunction "2_2") (pintype "passive"))
      (node (ref "U5") (pin "4") (pinfunction "BYP_4") (pintype "bidirectional"))
    )
    (net (code "72") (name "Net-(USB1-CC1)") (class "Default")
      (node (ref "R32") (pin "1") (pinfunction "1_1") (pintype "passive"))
      (node (ref "USB1") (pin "A5") (pinfunction "CC1_A5") (pintype "bidirectional"))
    )
    (net (code "73") (name "Net-(USB1-CC2)") (class "Default")
      (node (ref "R31") (pin "1") (pinfunction "1_1") (pintype "passive"))
      (node (ref "USB1") (pin "B5") (pinfunction "CC2_B5") (pintype "bidirectional"))
    )
    (net (code "74") (name "Net-(X1-X1)") (class "Default")
      (node (ref "C19") (pin "1") (pinfunction "1_1") (pintype "passive"))
      (node (ref "R34") (pin "1") (pinfunction "1_1") (pintype "passive"))
      (node (ref "X1") (pin "1") (pinfunction "X1_1") (pintype "bidirectional"))
    )
    (net (code "75") (name "unconnected-(J1-Pad15)") (class "Default")
      (node (ref "J1") (pin "15") (pinfunction "15_15") (pintype "bidirectional"))
    )
    (net (code "76") (name "unconnected-(J1-Pad16)") (class "Default")
      (node (ref "J1") (pin "16") (pinfunction "16_16") (pintype "bidirectional"))
    )
    (net (code "77") (name "unconnected-(J5-Pad1)") (class "Default")
      (node (ref "J5") (pin "1") (pinfunction "1_1") (pintype "bidirectional"))
    )
    (net (code "78") (name "unconnected-(J5-Pad2)") (class "Default")
      (node (ref "J5") (pin "2") (pinfunction "2_2") (pintype "bidirectional"))
    )
    (net (code "79") (name "unconnected-(J5-Pad24)") (class "Default")
      (node (ref "J5") (pin "24") (pinfunction "24_24") (pintype "bidirectional"))
    )
    (net (code "80") (name "unconnected-(U3-GPIO33-Pad38)") (class "Default")
      (node (ref "U3") (pin "38") (pinfunction "GPIO33_38") (pintype "bidirectional"))
    )
    (net (code "81") (name "unconnected-(U3-GPIO34-Pad39)") (class "Default")
      (node (ref "U3") (pin "39") (pinfunction "GPIO34_39") (pintype "bidirectional"))
    )
    (net (code "82") (name "unconnected-(U3-GPIO35-Pad40)") (class "Default")
      (node (ref "U3") (pin "40") (pinfunction "GPIO35_40") (pintype "bidirectional"))
    )
    (net (code "83") (name "unconnected-(U3-GPIO36-Pad41)") (class "Default")
      (node (ref "U3") (pin "41") (pinfunction "GPIO36_41") (pintype "bidirectional"))
    )
    (net (code "84") (name "unconnected-(U3-GPIO37-Pad42)") (class "Default")
      (node (ref "U3") (pin "42") (pinfunction "GPIO37_42") (pintype "bidirectional"))
    )
    (net (code "85") (name "unconnected-(U10-BYP-Pad4)") (class "Default")
      (node (ref "U10") (pin "4") (pinfunction "BYP_4") (pintype "bidirectional"))
    )
    (net (code "86") (name "unconnected-(U16-BYP-Pad4)") (class "Default")
      (node (ref "U16") (pin "4") (pinfunction "BYP_4") (pintype "bidirectional"))
    )
  )
)
